# ServoBoard.net
KiCad netlist of a schematic drawn in Altium Designer
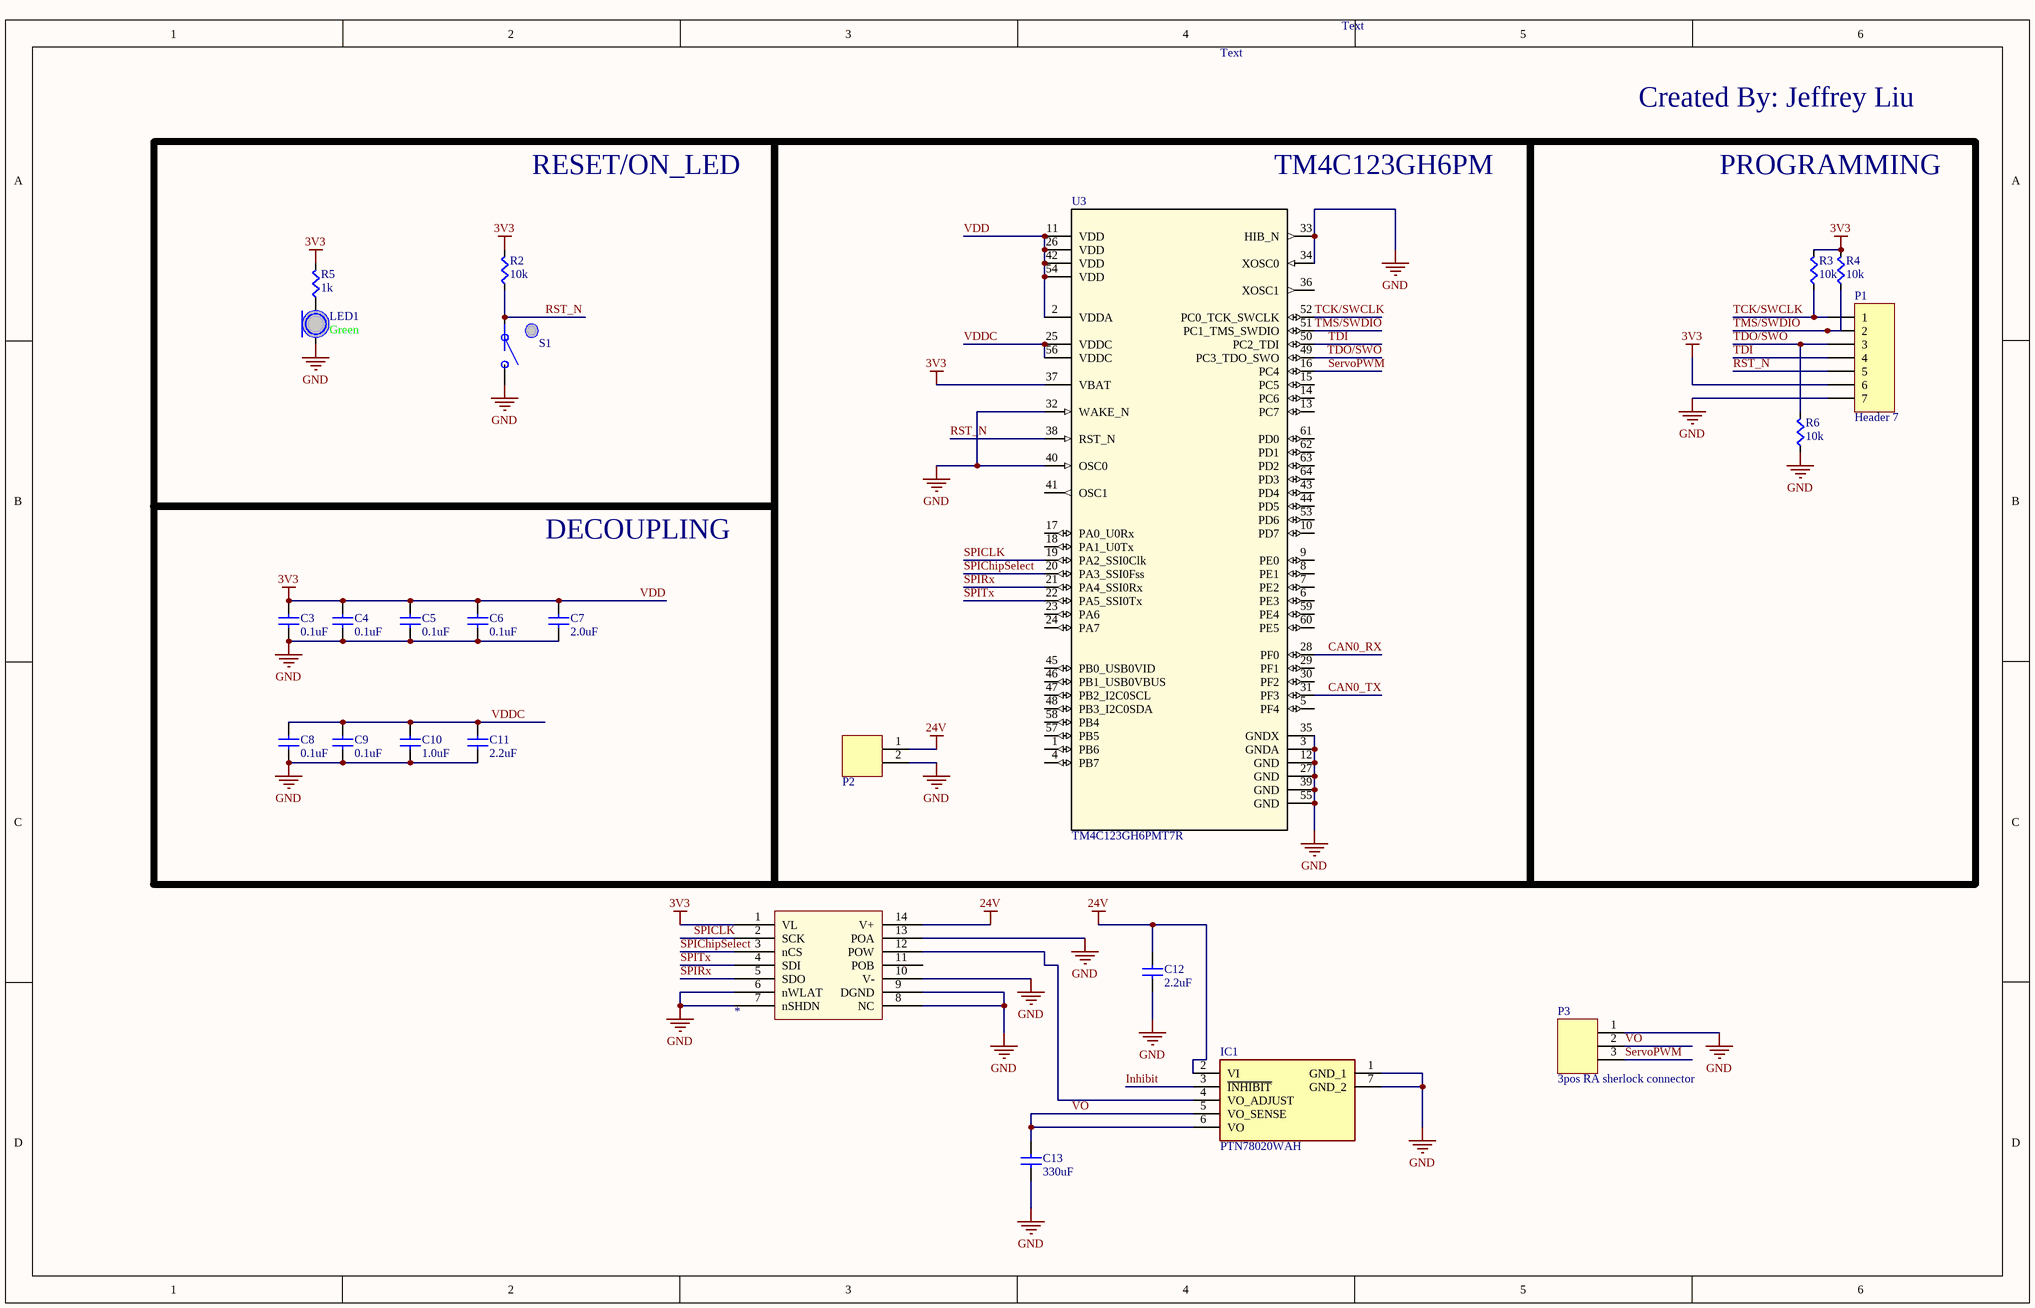
[diagram p0: ServoBoard.SchDoc]

(export (version "E")
  (design (tool "Eeschema 10.0.6"))
  (components
    (comp (ref "*")
      (value "MCP41HV31")
      (footprint "ICs:MCP41HV31 - duplicate2")
      (libsource (lib "ICs") (part "MCP41HV31"))
    )
    (comp (ref "C3")
      (value "0.1uF")
      (footprint "CAPC0603")
      (fields (field (name "Comment") "Cap"))
      (libsource (lib "SubjuGator8") (part "Cap"))
    )
    (comp (ref "C4")
      (value "0.1uF")
      (footprint "CAPC0603")
      (fields (field (name "Comment") "Cap"))
      (libsource (lib "SubjuGator8") (part "Cap"))
    )
    (comp (ref "C5")
      (value "0.1uF")
      (footprint "CAPC0603")
      (fields (field (name "Comment") "Cap"))
      (libsource (lib "SubjuGator8") (part "Cap"))
    )
    (comp (ref "C6")
      (value "0.1uF")
      (footprint "CAPC0603")
      (fields (field (name "Comment") "Cap"))
      (libsource (lib "SubjuGator8") (part "Cap"))
    )
    (comp (ref "C7")
      (value "2.0uF")
      (footprint "CAPC0603")
      (fields (field (name "Comment") "Cap"))
      (libsource (lib "SubjuGator8") (part "Cap"))
    )
    (comp (ref "C8")
      (value "0.1uF")
      (footprint "CAPC0603")
      (fields (field (name "Comment") "Cap"))
      (libsource (lib "SubjuGator8") (part "Cap"))
    )
    (comp (ref "C9")
      (value "0.1uF")
      (footprint "CAPC0603")
      (fields (field (name "Comment") "Cap"))
      (libsource (lib "SubjuGator8") (part "Cap"))
    )
    (comp (ref "C10")
      (value "1.0uF")
      (footprint "CAPC0603")
      (fields (field (name "Comment") "Cap"))
      (libsource (lib "SubjuGator8") (part "Cap"))
    )
    (comp (ref "C11")
      (value "2.2uF")
      (footprint "CAPC0603")
      (fields (field (name "Comment") "Cap"))
      (libsource (lib "SubjuGator8") (part "Cap"))
    )
    (comp (ref "C12")
      (value "2.2uF")
      (footprint "CAPC1206")
      (fields (field (name "Comment") "Cap"))
      (libsource (lib "Passives") (part "Cap"))
    )
    (comp (ref "C13")
      (value "330uF")
      (footprint "CAPC0603")
      (fields (field (name "Comment") "Cap"))
      (libsource (lib "Passives") (part "Cap"))
    )
    (comp (ref "IC1")
      (value "PTN78020WAH")
      (footprint "SamacSys:EUL(R-PDSS-B7)")
      (description "Integrated Circuit")
      (fields
        (field (name "MOUSER PART NUMBER") "595-PTN78020WAH")
        (field (name "RS PART NUMBER") "5457849P")
      )
      (libsource (lib "*") (part "PTN78020WAH"))
    )
    (comp (ref "LED1")
      (value "LED")
      (footprint "LED0603")
      (fields (field (name "COLOR") "Green"))
      (libsource (lib "SubjuGator8") (part "LED"))
    )
    (comp (ref "P1")
      (value "Header 7")
      (footprint "HDR1X7")
      (description "Header, 7-Pin")
      (fields (field (name "PUBLISHER") "Altium Limited"))
      (libsource (lib "Miscellaneous Connectors") (part "Header 7"))
    )
    (comp (ref "P2")
      (value "2-pin Horz Sherlock")
      (footprint "MOLEX-HDR-1X2-SHERLOCK-HORZ")
      (fields
        (field (name "MANUFACTURER PART NUMBER") "0353630260")
        (field (name "MANUFACTURER") "Molex Inc")
      )
      (libsource (lib "Connectors") (part "MOLEX-HDR-1x2-SHERLOCK_RA"))
    )
    (comp (ref "P3")
      (value "3pos RA sherlock connector")
      (footprint "MOLEX-HDR-1X3-SHERLOCK-RA")
      (description "Header, Molex, 2mm Pitch Sherlock Header, Single Row, Right Angle 3 Circuits, Length 3.3mm")
      (fields
        (field (name "MANUFACTURER PART NUMBER") "35363-0360")
        (field (name "MANUFACTURER") "Molex Connector Corporation")
      )
      (libsource (lib "Connectors") (part "MOLEX-HDR-1x3-SHERLOCK_RA"))
    )
    (comp (ref "R2")
      (value "10k")
      (footprint "RES0603")
      (fields (field (name "Comment") "Res"))
      (libsource (lib "SubjuGator8") (part "Res"))
    )
    (comp (ref "R3")
      (value "10k")
      (footprint "RES0603")
      (fields (field (name "Comment") "Res"))
      (libsource (lib "SubjuGator8") (part "Res"))
    )
    (comp (ref "R4")
      (value "10k")
      (footprint "RES0603")
      (fields (field (name "Comment") "Res"))
      (libsource (lib "SubjuGator8") (part "Res"))
    )
    (comp (ref "R5")
      (value "1k")
      (footprint "RES0603")
      (fields (field (name "Comment") "Res"))
      (libsource (lib "SubjuGator8") (part "Res"))
    )
    (comp (ref "R6")
      (value "10k")
      (footprint "RES0603")
      (fields (field (name "Comment") "Res"))
      (libsource (lib "SubjuGator8") (part "Res"))
    )
    (comp (ref "S1")
      (value "Button")
      (footprint "PTS645xxxxSMTR92")
      (description "SPST Button")
      (libsource (lib "SubjuGator8") (part "Button"))
    )
    (comp (ref "U3")
      (value "TM4C123GH6PMT7R")
      (footprint "TM4C123GH6PMT7R_L")
      (description "Imported")
      (fields
        (field (name "PARTNUMBER") "TM4C123GH6PMTR")
        (field (name "ALTERNATE_PARTNUMBER") "TM4C123GH6PMT")
      )
      (libsource (lib "ICs") (part "TM4C123GH6PMT7R"))
    )
  )
  (nets
    (net (code "1") (name "/CAN0_RX") (class "Default")
      (node (ref "U3") (pin "28") (pinfunction "PF0_28") (pintype "bidirectional"))
    )
    (net (code "2") (name "/CAN0_TX") (class "Default")
      (node (ref "U3") (pin "31") (pinfunction "PF3_31") (pintype "bidirectional"))
    )
    (net (code "3") (name "/Inhibit") (class "Default")
      (node (ref "IC1") (pin "3") (pinfunction "~{INHIBIT}_3") (pintype "passive"))
    )
    (net (code "4") (name "/RST_N") (class "Default")
      (node (ref "P1") (pin "5") (pinfunction "5_5") (pintype "passive"))
      (node (ref "R2") (pin "2") (pinfunction "B_2") (pintype "passive"))
      (node (ref "S1") (pin "A") (pinfunction "A_A") (pintype "passive"))
      (node (ref "U3") (pin "38") (pinfunction "RST_N_38") (pintype "input"))
    )
    (net (code "5") (name "/SPICLK") (class "Default")
      (node (ref "*") (pin "2") (pinfunction "SCK_2") (pintype "passive"))
      (node (ref "U3") (pin "19") (pinfunction "PA2_SSI0Clk_19") (pintype "bidirectional"))
    )
    (net (code "6") (name "/SPIChipSelect") (class "Default")
      (node (ref "*") (pin "3") (pinfunction "nCS_3") (pintype "passive"))
      (node (ref "U3") (pin "20") (pinfunction "PA3_SSI0Fss_20") (pintype "bidirectional"))
    )
    (net (code "7") (name "/SPIRx") (class "Default")
      (node (ref "*") (pin "5") (pinfunction "SDO_5") (pintype "passive"))
      (node (ref "U3") (pin "21") (pinfunction "PA4_SSI0Rx_21") (pintype "bidirectional"))
    )
    (net (code "8") (name "/SPITx") (class "Default")
      (node (ref "*") (pin "4") (pinfunction "SDI_4") (pintype "passive"))
      (node (ref "U3") (pin "22") (pinfunction "PA5_SSI0Tx_22") (pintype "bidirectional"))
    )
    (net (code "9") (name "/ServoPWM") (class "Default")
      (node (ref "P3") (pin "3") (pinfunction "3_3") (pintype "passive"))
      (node (ref "U3") (pin "16") (pinfunction "PC4_16") (pintype "bidirectional"))
    )
    (net (code "10") (name "/TCK{slash}SWCLK") (class "Default")
      (node (ref "P1") (pin "1") (pinfunction "1_1") (pintype "passive"))
      (node (ref "R3") (pin "2") (pinfunction "B_2") (pintype "passive"))
      (node (ref "U3") (pin "52") (pinfunction "PC0_TCK_SWCLK_52") (pintype "bidirectional"))
    )
    (net (code "11") (name "/TDI") (class "Default")
      (node (ref "P1") (pin "4") (pinfunction "4_4") (pintype "passive"))
      (node (ref "U3") (pin "50") (pinfunction "PC2_TDI_50") (pintype "bidirectional"))
    )
    (net (code "12") (name "/TDO{slash}SWO") (class "Default")
      (node (ref "P1") (pin "3") (pinfunction "3_3") (pintype "passive"))
      (node (ref "R6") (pin "1") (pinfunction "A_1") (pintype "passive"))
      (node (ref "U3") (pin "49") (pinfunction "PC3_TDO_SWO_49") (pintype "bidirectional"))
    )
    (net (code "13") (name "/TMS{slash}SWDIO") (class "Default")
      (node (ref "P1") (pin "2") (pinfunction "2_2") (pintype "passive"))
      (node (ref "R4") (pin "2") (pinfunction "B_2") (pintype "passive"))
      (node (ref "U3") (pin "51") (pinfunction "PC1_TMS_SWDIO_51") (pintype "bidirectional"))
    )
    (net (code "14") (name "/VDDC") (class "Default")
      (node (ref "C10") (pin "1") (pinfunction "A_1") (pintype "passive"))
      (node (ref "C11") (pin "1") (pinfunction "A_1") (pintype "passive"))
      (node (ref "C8") (pin "1") (pinfunction "A_1") (pintype "passive"))
      (node (ref "C9") (pin "1") (pinfunction "A_1") (pintype "passive"))
      (node (ref "U3") (pin "25") (pinfunction "VDDC_25") (pintype "power_in"))
      (node (ref "U3") (pin "56") (pinfunction "VDDC_56") (pintype "power_in"))
    )
    (net (code "15") (name "/VO") (class "Default")
      (node (ref "C13") (pin "1") (pinfunction "A_1") (pintype "passive"))
      (node (ref "IC1") (pin "5") (pinfunction "VO_SENSE_5") (pintype "passive"))
      (node (ref "IC1") (pin "6") (pinfunction "VO_6") (pintype "passive"))
      (node (ref "P3") (pin "2") (pinfunction "2_2") (pintype "passive"))
    )
    (net (code "16") (name "3V3") (class "Default")
      (node (ref "*") (pin "1") (pinfunction "VL_1") (pintype "passive"))
      (node (ref "C3") (pin "1") (pinfunction "A_1") (pintype "passive"))
      (node (ref "C4") (pin "1") (pinfunction "A_1") (pintype "passive"))
      (node (ref "C5") (pin "1") (pinfunction "A_1") (pintype "passive"))
      (node (ref "C6") (pin "1") (pinfunction "A_1") (pintype "passive"))
      (node (ref "C7") (pin "1") (pinfunction "A_1") (pintype "passive"))
      (node (ref "P1") (pin "6") (pinfunction "6_6") (pintype "passive"))
      (node (ref "R2") (pin "1") (pinfunction "A_1") (pintype "passive"))
      (node (ref "R3") (pin "1") (pinfunction "A_1") (pintype "passive"))
      (node (ref "R4") (pin "1") (pinfunction "A_1") (pintype "passive"))
      (node (ref "R5") (pin "1") (pinfunction "A_1") (pintype "passive"))
      (node (ref "U3") (pin "11") (pinfunction "VDD_11") (pintype "power_in"))
      (node (ref "U3") (pin "2") (pinfunction "VDDA_2") (pintype "power_in"))
      (node (ref "U3") (pin "26") (pinfunction "VDD_26") (pintype "power_in"))
      (node (ref "U3") (pin "37") (pinfunction "VBAT_37") (pintype "power_in"))
      (node (ref "U3") (pin "42") (pinfunction "VDD_42") (pintype "power_in"))
      (node (ref "U3") (pin "54") (pinfunction "VDD_54") (pintype "power_in"))
    )
    (net (code "17") (name "24V") (class "Default")
      (node (ref "*") (pin "14") (pinfunction "V+_14") (pintype "passive"))
      (node (ref "C12") (pin "1") (pinfunction "A_1") (pintype "passive"))
      (node (ref "IC1") (pin "2") (pinfunction "VI_2") (pintype "passive"))
      (node (ref "P2") (pin "1") (pinfunction "1_1") (pintype "passive"))
    )
    (net (code "18") (name "GND") (class "Default")
      (node (ref "*") (pin "10") (pinfunction "V-_10") (pintype "passive"))
      (node (ref "*") (pin "13") (pinfunction "POA_13") (pintype "passive"))
      (node (ref "*") (pin "6") (pinfunction "nWLAT_6") (pintype "passive"))
      (node (ref "*") (pin "7") (pinfunction "nSHDN_7") (pintype "passive"))
      (node (ref "*") (pin "8") (pinfunction "NC_8") (pintype "passive"))
      (node (ref "*") (pin "9") (pinfunction "DGND_9") (pintype "passive"))
      (node (ref "C10") (pin "2") (pinfunction "B_2") (pintype "passive"))
      (node (ref "C11") (pin "2") (pinfunction "B_2") (pintype "passive"))
      (node (ref "C12") (pin "2") (pinfunction "B_2") (pintype "passive"))
      (node (ref "C13") (pin "2") (pinfunction "B_2") (pintype "passive"))
      (node (ref "C3") (pin "2") (pinfunction "B_2") (pintype "passive"))
      (node (ref "C4") (pin "2") (pinfunction "B_2") (pintype "passive"))
      (node (ref "C5") (pin "2") (pinfunction "B_2") (pintype "passive"))
      (node (ref "C6") (pin "2") (pinfunction "B_2") (pintype "passive"))
      (node (ref "C7") (pin "2") (pinfunction "B_2") (pintype "passive"))
      (node (ref "C8") (pin "2") (pinfunction "B_2") (pintype "passive"))
      (node (ref "C9") (pin "2") (pinfunction "B_2") (pintype "passive"))
      (node (ref "IC1") (pin "1") (pinfunction "GND_1_1") (pintype "passive"))
      (node (ref "IC1") (pin "7") (pinfunction "GND_2_7") (pintype "passive"))
      (node (ref "LED1") (pin "C") (pinfunction "C_C") (pintype "passive"))
      (node (ref "P1") (pin "7") (pinfunction "7_7") (pintype "passive"))
      (node (ref "P2") (pin "2") (pinfunction "2_2") (pintype "passive"))
      (node (ref "P3") (pin "1") (pinfunction "1_1") (pintype "passive"))
      (node (ref "R6") (pin "2") (pinfunction "B_2") (pintype "passive"))
      (node (ref "S1") (pin "B") (pinfunction "B_B") (pintype "passive"))
      (node (ref "U3") (pin "12") (pinfunction "GND_12") (pintype "power_in"))
      (node (ref "U3") (pin "27") (pinfunction "GND_27") (pintype "power_in"))
      (node (ref "U3") (pin "3") (pinfunction "GNDA_3") (pintype "power_in"))
      (node (ref "U3") (pin "32") (pinfunction "WAKE_N_32") (pintype "input"))
      (node (ref "U3") (pin "33") (pinfunction "HIB_N_33") (pintype "output"))
      (node (ref "U3") (pin "34") (pinfunction "XOSC0_34") (pintype "input"))
      (node (ref "U3") (pin "35") (pinfunction "GNDX_35") (pintype "power_in"))
      (node (ref "U3") (pin "39") (pinfunction "GND_39") (pintype "power_in"))
      (node (ref "U3") (pin "40") (pinfunction "OSC0_40") (pintype "input"))
      (node (ref "U3") (pin "55") (pinfunction "GND_55") (pintype "power_in"))
    )
    (net (code "19") (name "Net-(*-POW)") (class "Default")
      (node (ref "*") (pin "12") (pinfunction "POW_12") (pintype "passive"))
      (node (ref "IC1") (pin "4") (pinfunction "VO_ADJUST_4") (pintype "passive"))
    )
    (net (code "20") (name "Net-(R5-B)") (class "Default")
      (node (ref "LED1") (pin "A") (pinfunction "A_A") (pintype "passive"))
      (node (ref "R5") (pin "2") (pinfunction "B_2") (pintype "passive"))
    )
    (net (code "21") (name "unconnected-(*-POB-Pad11)") (class "Default")
      (node (ref "*") (pin "11") (pinfunction "POB_11") (pintype "passive"))
    )
    (net (code "22") (name "unconnected-(U3-OSC1-Pad41)") (class "Default")
      (node (ref "U3") (pin "41") (pinfunction "OSC1_41") (pintype "output"))
    )
    (net (code "23") (name "unconnected-(U3-PA0_U0Rx-Pad17)") (class "Default")
      (node (ref "U3") (pin "17") (pinfunction "PA0_U0Rx_17") (pintype "bidirectional"))
    )
    (net (code "24") (name "unconnected-(U3-PA1_U0Tx-Pad18)") (class "Default")
      (node (ref "U3") (pin "18") (pinfunction "PA1_U0Tx_18") (pintype "bidirectional"))
    )
    (net (code "25") (name "unconnected-(U3-PA6-Pad23)") (class "Default")
      (node (ref "U3") (pin "23") (pinfunction "PA6_23") (pintype "bidirectional"))
    )
    (net (code "26") (name "unconnected-(U3-PA7-Pad24)") (class "Default")
      (node (ref "U3") (pin "24") (pinfunction "PA7_24") (pintype "bidirectional"))
    )
    (net (code "27") (name "unconnected-(U3-PB0_USB0VID-Pad45)") (class "Default")
      (node (ref "U3") (pin "45") (pinfunction "PB0_USB0VID_45") (pintype "bidirectional"))
    )
    (net (code "28") (name "unconnected-(U3-PB1_USB0VBUS-Pad46)") (class "Default")
      (node (ref "U3") (pin "46") (pinfunction "PB1_USB0VBUS_46") (pintype "bidirectional"))
    )
    (net (code "29") (name "unconnected-(U3-PB2_I2C0SCL-Pad47)") (class "Default")
      (node (ref "U3") (pin "47") (pinfunction "PB2_I2C0SCL_47") (pintype "bidirectional"))
    )
    (net (code "30") (name "unconnected-(U3-PB3_I2C0SDA-Pad48)") (class "Default")
      (node (ref "U3") (pin "48") (pinfunction "PB3_I2C0SDA_48") (pintype "bidirectional"))
    )
    (net (code "31") (name "unconnected-(U3-PB4-Pad58)") (class "Default")
      (node (ref "U3") (pin "58") (pinfunction "PB4_58") (pintype "bidirectional"))
    )
    (net (code "32") (name "unconnected-(U3-PB5-Pad57)") (class "Default")
      (node (ref "U3") (pin "57") (pinfunction "PB5_57") (pintype "bidirectional"))
    )
    (net (code "33") (name "unconnected-(U3-PB6-Pad1)") (class "Default")
      (node (ref "U3") (pin "1") (pinfunction "PB6_1") (pintype "bidirectional"))
    )
    (net (code "34") (name "unconnected-(U3-PB7-Pad4)") (class "Default")
      (node (ref "U3") (pin "4") (pinfunction "PB7_4") (pintype "bidirectional"))
    )
    (net (code "35") (name "unconnected-(U3-PC5-Pad15)") (class "Default")
      (node (ref "U3") (pin "15") (pinfunction "PC5_15") (pintype "bidirectional"))
    )
    (net (code "36") (name "unconnected-(U3-PC6-Pad14)") (class "Default")
      (node (ref "U3") (pin "14") (pinfunction "PC6_14") (pintype "bidirectional"))
    )
    (net (code "37") (name "unconnected-(U3-PC7-Pad13)") (class "Default")
      (node (ref "U3") (pin "13") (pinfunction "PC7_13") (pintype "bidirectional"))
    )
    (net (code "38") (name "unconnected-(U3-PD0-Pad61)") (class "Default")
      (node (ref "U3") (pin "61") (pinfunction "PD0_61") (pintype "bidirectional"))
    )
    (net (code "39") (name "unconnected-(U3-PD1-Pad62)") (class "Default")
      (node (ref "U3") (pin "62") (pinfunction "PD1_62") (pintype "bidirectional"))
    )
    (net (code "40") (name "unconnected-(U3-PD2-Pad63)") (class "Default")
      (node (ref "U3") (pin "63") (pinfunction "PD2_63") (pintype "bidirectional"))
    )
    (net (code "41") (name "unconnected-(U3-PD3-Pad64)") (class "Default")
      (node (ref "U3") (pin "64") (pinfunction "PD3_64") (pintype "bidirectional"))
    )
    (net (code "42") (name "unconnected-(U3-PD4-Pad43)") (class "Default")
      (node (ref "U3") (pin "43") (pinfunction "PD4_43") (pintype "bidirectional"))
    )
    (net (code "43") (name "unconnected-(U3-PD5-Pad44)") (class "Default")
      (node (ref "U3") (pin "44") (pinfunction "PD5_44") (pintype "bidirectional"))
    )
    (net (code "44") (name "unconnected-(U3-PD6-Pad53)") (class "Default")
      (node (ref "U3") (pin "53") (pinfunction "PD6_53") (pintype "bidirectional"))
    )
    (net (code "45") (name "unconnected-(U3-PD7-Pad10)") (class "Default")
      (node (ref "U3") (pin "10") (pinfunction "PD7_10") (pintype "bidirectional"))
    )
    (net (code "46") (name "unconnected-(U3-PE0-Pad9)") (class "Default")
      (node (ref "U3") (pin "9") (pinfunction "PE0_9") (pintype "bidirectional"))
    )
    (net (code "47") (name "unconnected-(U3-PE1-Pad8)") (class "Default")
      (node (ref "U3") (pin "8") (pinfunction "PE1_8") (pintype "bidirectional"))
    )
    (net (code "48") (name "unconnected-(U3-PE2-Pad7)") (class "Default")
      (node (ref "U3") (pin "7") (pinfunction "PE2_7") (pintype "bidirectional"))
    )
    (net (code "49") (name "unconnected-(U3-PE3-Pad6)") (class "Default")
      (node (ref "U3") (pin "6") (pinfunction "PE3_6") (pintype "bidirectional"))
    )
    (net (code "50") (name "unconnected-(U3-PE4-Pad59)") (class "Default")
      (node (ref "U3") (pin "59") (pinfunction "PE4_59") (pintype "bidirectional"))
    )
    (net (code "51") (name "unconnected-(U3-PE5-Pad60)") (class "Default")
      (node (ref "U3") (pin "60") (pinfunction "PE5_60") (pintype "bidirectional"))
    )
    (net (code "52") (name "unconnected-(U3-PF1-Pad29)") (class "Default")
      (node (ref "U3") (pin "29") (pinfunction "PF1_29") (pintype "bidirectional"))
    )
    (net (code "53") (name "unconnected-(U3-PF2-Pad30)") (class "Default")
      (node (ref "U3") (pin "30") (pinfunction "PF2_30") (pintype "bidirectional"))
    )
    (net (code "54") (name "unconnected-(U3-PF4-Pad5)") (class "Default")
      (node (ref "U3") (pin "5") (pinfunction "PF4_5") (pintype "bidirectional"))
    )
    (net (code "55") (name "unconnected-(U3-XOSC1-Pad36)") (class "Default")
      (node (ref "U3") (pin "36") (pinfunction "XOSC1_36") (pintype "output"))
    )
  )
)
